# outin_shield_ethernet.net
KiCad netlist of a schematic drawn in EAGLE
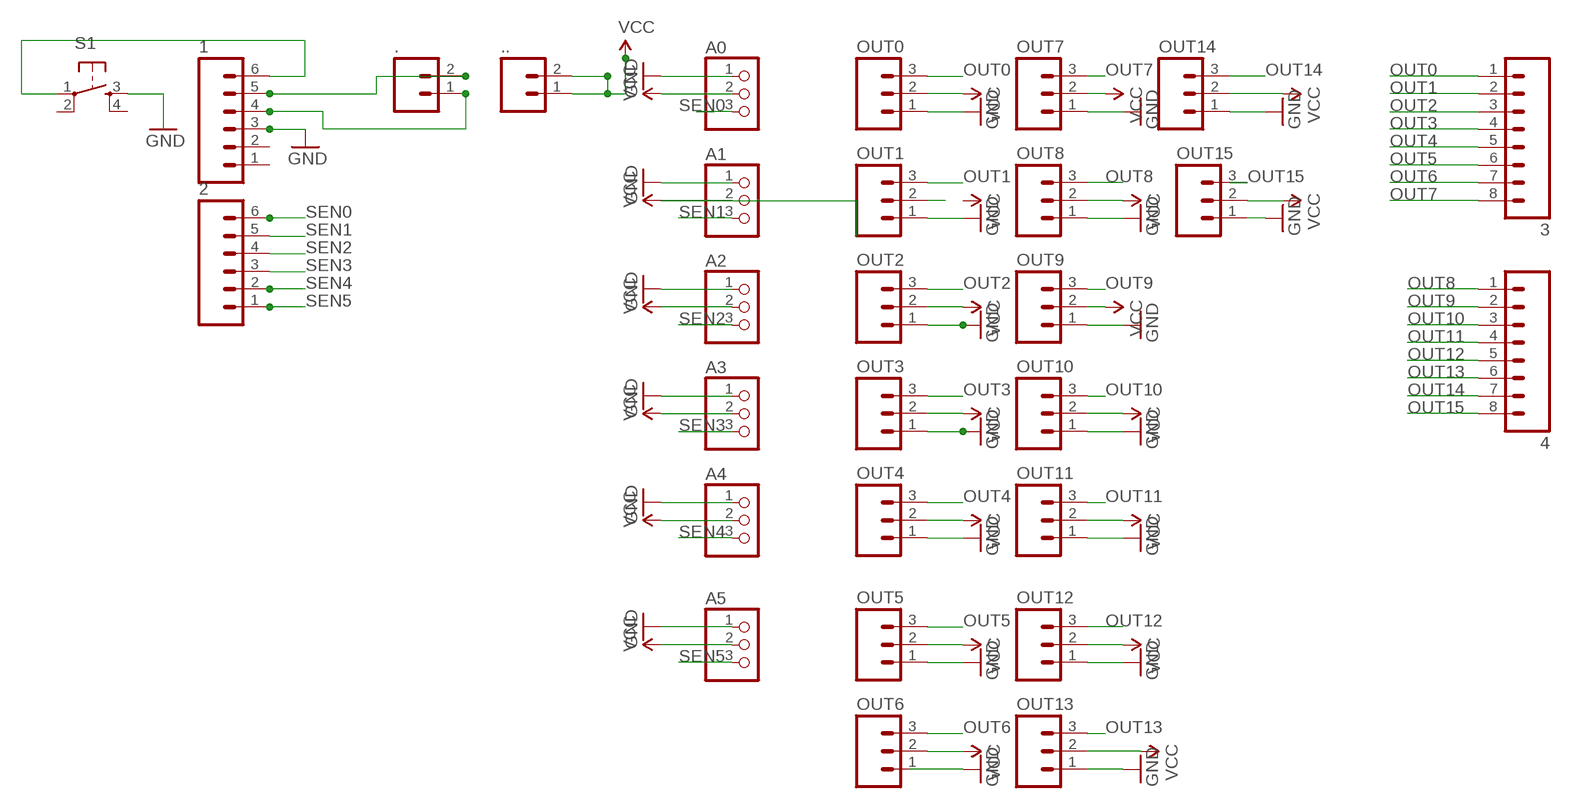
[diagram p0: schematic, sheet 1]

(export (version "E")
  (design (tool "Eeschema 10.0.6"))
  (components
    (comp (ref ".")
      (value "M02LOCK")
      (footprint "eagle-import:1X02_LOCK")
      (libsource (lib "eagle-import") (part "M02LOCK"))
    )
    (comp (ref "..")
      (value "M02LOCK")
      (footprint "eagle-import:1X02_LOCK")
      (libsource (lib "eagle-import") (part "M02LOCK"))
    )
    (comp (ref "1")
      (value "M06SIP")
      (footprint "eagle-import:1X06")
      (libsource (lib "eagle-import") (part "M06SIP"))
    )
    (comp (ref "2")
      (value "M06SIP")
      (footprint "eagle-import:1X06")
      (libsource (lib "eagle-import") (part "M06SIP"))
    )
    (comp (ref "3")
      (value "M081X08")
      (footprint "eagle-import:1X08")
      (libsource (lib "eagle-import") (part "M081X08"))
    )
    (comp (ref "4")
      (value "M081X08")
      (footprint "eagle-import:1X08")
      (libsource (lib "eagle-import") (part "M081X08"))
    )
    (comp (ref "A0")
      (value "PINHD-1X3")
      (footprint "eagle-import:1X03")
      (libsource (lib "eagle-import") (part "PINHD-1X3"))
    )
    (comp (ref "A1")
      (value "PINHD-1X3")
      (footprint "eagle-import:1X03")
      (libsource (lib "eagle-import") (part "PINHD-1X3"))
    )
    (comp (ref "A2")
      (value "PINHD-1X3")
      (footprint "eagle-import:1X03")
      (libsource (lib "eagle-import") (part "PINHD-1X3"))
    )
    (comp (ref "A3")
      (value "PINHD-1X3")
      (footprint "eagle-import:1X03")
      (libsource (lib "eagle-import") (part "PINHD-1X3"))
    )
    (comp (ref "A4")
      (value "PINHD-1X3")
      (footprint "eagle-import:1X03")
      (libsource (lib "eagle-import") (part "PINHD-1X3"))
    )
    (comp (ref "A5")
      (value "PINHD-1X3")
      (footprint "eagle-import:1X03")
      (libsource (lib "eagle-import") (part "PINHD-1X3"))
    )
    (comp (ref "OUT0")
      (value "M03PTH")
      (footprint "eagle-import:1X03")
      (libsource (lib "eagle-import") (part "M03PTH"))
    )
    (comp (ref "OUT1")
      (value "M03PTH")
      (footprint "eagle-import:1X03")
      (libsource (lib "eagle-import") (part "M03PTH"))
    )
    (comp (ref "OUT2")
      (value "M03PTH")
      (footprint "eagle-import:1X03")
      (libsource (lib "eagle-import") (part "M03PTH"))
    )
    (comp (ref "OUT3")
      (value "M03PTH")
      (footprint "eagle-import:1X03")
      (libsource (lib "eagle-import") (part "M03PTH"))
    )
    (comp (ref "OUT4")
      (value "M03PTH")
      (footprint "eagle-import:1X03")
      (libsource (lib "eagle-import") (part "M03PTH"))
    )
    (comp (ref "OUT5")
      (value "M03PTH")
      (footprint "eagle-import:1X03")
      (libsource (lib "eagle-import") (part "M03PTH"))
    )
    (comp (ref "OUT6")
      (value "M03PTH")
      (footprint "eagle-import:1X03")
      (libsource (lib "eagle-import") (part "M03PTH"))
    )
    (comp (ref "OUT7")
      (value "M03PTH")
      (footprint "eagle-import:1X03")
      (libsource (lib "eagle-import") (part "M03PTH"))
    )
    (comp (ref "OUT8")
      (value "M03PTH")
      (footprint "eagle-import:1X03")
      (libsource (lib "eagle-import") (part "M03PTH"))
    )
    (comp (ref "OUT9")
      (value "M03PTH")
      (footprint "eagle-import:1X03")
      (libsource (lib "eagle-import") (part "M03PTH"))
    )
    (comp (ref "OUT10")
      (value "M03PTH")
      (footprint "eagle-import:1X03")
      (libsource (lib "eagle-import") (part "M03PTH"))
    )
    (comp (ref "OUT11")
      (value "M03PTH")
      (footprint "eagle-import:1X03")
      (libsource (lib "eagle-import") (part "M03PTH"))
    )
    (comp (ref "OUT12")
      (value "M03PTH")
      (footprint "eagle-import:1X03")
      (libsource (lib "eagle-import") (part "M03PTH"))
    )
    (comp (ref "OUT13")
      (value "M03PTH")
      (footprint "eagle-import:1X03")
      (libsource (lib "eagle-import") (part "M03PTH"))
    )
    (comp (ref "OUT14")
      (value "M03PTH")
      (footprint "eagle-import:1X03")
      (libsource (lib "eagle-import") (part "M03PTH"))
    )
    (comp (ref "OUT15")
      (value "M03PTH")
      (footprint "eagle-import:1X03")
      (libsource (lib "eagle-import") (part "M03PTH"))
    )
    (comp (ref "S1")
      (value "TAC_SWITCHPTH")
      (footprint "eagle-import:TACTILE-PTH")
      (libsource (lib "eagle-import") (part "TAC_SWITCHPTH"))
    )
  )
  (nets
    (net (code "1") (name "/OUT0") (class "Default")
      (node (ref "3") (pin "1") (pinfunction "1_1") (pintype "passive"))
      (node (ref "OUT0") (pin "3") (pinfunction "3_3") (pintype "passive"))
    )
    (net (code "2") (name "/OUT1") (class "Default")
      (node (ref "3") (pin "2") (pinfunction "2_2") (pintype "passive"))
      (node (ref "OUT1") (pin "3") (pinfunction "3_3") (pintype "passive"))
    )
    (net (code "3") (name "/OUT2") (class "Default")
      (node (ref "3") (pin "3") (pinfunction "3_3") (pintype "passive"))
      (node (ref "OUT2") (pin "3") (pinfunction "3_3") (pintype "passive"))
    )
    (net (code "4") (name "/OUT3") (class "Default")
      (node (ref "3") (pin "4") (pinfunction "4_4") (pintype "passive"))
      (node (ref "OUT3") (pin "3") (pinfunction "3_3") (pintype "passive"))
    )
    (net (code "5") (name "/OUT4") (class "Default")
      (node (ref "3") (pin "5") (pinfunction "5_5") (pintype "passive"))
      (node (ref "OUT4") (pin "3") (pinfunction "3_3") (pintype "passive"))
    )
    (net (code "6") (name "/OUT5") (class "Default")
      (node (ref "3") (pin "6") (pinfunction "6_6") (pintype "passive"))
      (node (ref "OUT5") (pin "3") (pinfunction "3_3") (pintype "passive"))
    )
    (net (code "7") (name "/OUT6") (class "Default")
      (node (ref "3") (pin "7") (pinfunction "7_7") (pintype "passive"))
      (node (ref "OUT6") (pin "3") (pinfunction "3_3") (pintype "passive"))
    )
    (net (code "8") (name "/OUT7") (class "Default")
      (node (ref "3") (pin "8") (pinfunction "8_8") (pintype "passive"))
      (node (ref "OUT7") (pin "3") (pinfunction "3_3") (pintype "passive"))
    )
    (net (code "9") (name "/OUT8") (class "Default")
      (node (ref "4") (pin "1") (pinfunction "1_1") (pintype "passive"))
      (node (ref "OUT8") (pin "3") (pinfunction "3_3") (pintype "passive"))
    )
    (net (code "10") (name "/OUT9") (class "Default")
      (node (ref "4") (pin "2") (pinfunction "2_2") (pintype "passive"))
      (node (ref "OUT9") (pin "3") (pinfunction "3_3") (pintype "passive"))
    )
    (net (code "11") (name "/OUT10") (class "Default")
      (node (ref "4") (pin "3") (pinfunction "3_3") (pintype "passive"))
      (node (ref "OUT10") (pin "3") (pinfunction "3_3") (pintype "passive"))
    )
    (net (code "12") (name "/OUT11") (class "Default")
      (node (ref "4") (pin "4") (pinfunction "4_4") (pintype "passive"))
      (node (ref "OUT11") (pin "3") (pinfunction "3_3") (pintype "passive"))
    )
    (net (code "13") (name "/OUT12") (class "Default")
      (node (ref "4") (pin "5") (pinfunction "5_5") (pintype "passive"))
      (node (ref "OUT12") (pin "3") (pinfunction "3_3") (pintype "passive"))
    )
    (net (code "14") (name "/OUT13") (class "Default")
      (node (ref "4") (pin "6") (pinfunction "6_6") (pintype "passive"))
      (node (ref "OUT13") (pin "3") (pinfunction "3_3") (pintype "passive"))
    )
    (net (code "15") (name "/OUT14") (class "Default")
      (node (ref "4") (pin "7") (pinfunction "7_7") (pintype "passive"))
      (node (ref "OUT14") (pin "3") (pinfunction "3_3") (pintype "passive"))
    )
    (net (code "16") (name "/OUT15") (class "Default")
      (node (ref "4") (pin "8") (pinfunction "8_8") (pintype "passive"))
      (node (ref "OUT15") (pin "3") (pinfunction "3_3") (pintype "passive"))
    )
    (net (code "17") (name "/SEN0") (class "Default")
      (node (ref "2") (pin "6") (pinfunction "6_6") (pintype "passive"))
      (node (ref "A0") (pin "3") (pinfunction "3_3") (pintype "passive"))
    )
    (net (code "18") (name "/SEN1") (class "Default")
      (node (ref "2") (pin "5") (pinfunction "5_5") (pintype "passive"))
      (node (ref "A1") (pin "3") (pinfunction "3_3") (pintype "passive"))
    )
    (net (code "19") (name "/SEN2") (class "Default")
      (node (ref "2") (pin "4") (pinfunction "4_4") (pintype "passive"))
      (node (ref "A2") (pin "3") (pinfunction "3_3") (pintype "passive"))
    )
    (net (code "20") (name "/SEN3") (class "Default")
      (node (ref "2") (pin "3") (pinfunction "3_3") (pintype "passive"))
      (node (ref "A3") (pin "3") (pinfunction "3_3") (pintype "passive"))
    )
    (net (code "21") (name "/SEN4") (class "Default")
      (node (ref "2") (pin "2") (pinfunction "2_2") (pintype "passive"))
      (node (ref "A4") (pin "3") (pinfunction "3_3") (pintype "passive"))
    )
    (net (code "22") (name "/SEN5") (class "Default")
      (node (ref "2") (pin "1") (pinfunction "1_1") (pintype "passive"))
      (node (ref "A5") (pin "3") (pinfunction "3_3") (pintype "passive"))
    )
    (net (code "23") (name "GND") (class "Default")
      (node (ref "1") (pin "3") (pinfunction "3_3") (pintype "passive"))
      (node (ref "A0") (pin "1") (pinfunction "1_1") (pintype "passive"))
      (node (ref "A1") (pin "1") (pinfunction "1_1") (pintype "passive"))
      (node (ref "A2") (pin "1") (pinfunction "1_1") (pintype "passive"))
      (node (ref "A3") (pin "1") (pinfunction "1_1") (pintype "passive"))
      (node (ref "A4") (pin "1") (pinfunction "1_1") (pintype "passive"))
      (node (ref "A5") (pin "1") (pinfunction "1_1") (pintype "passive"))
      (node (ref "OUT0") (pin "1") (pinfunction "1_1") (pintype "passive"))
      (node (ref "OUT1") (pin "1") (pinfunction "1_1") (pintype "passive"))
      (node (ref "OUT10") (pin "1") (pinfunction "1_1") (pintype "passive"))
      (node (ref "OUT11") (pin "1") (pinfunction "1_1") (pintype "passive"))
      (node (ref "OUT12") (pin "1") (pinfunction "1_1") (pintype "passive"))
      (node (ref "OUT13") (pin "1") (pinfunction "1_1") (pintype "passive"))
      (node (ref "OUT14") (pin "1") (pinfunction "1_1") (pintype "passive"))
      (node (ref "OUT15") (pin "1") (pinfunction "1_1") (pintype "passive"))
      (node (ref "OUT2") (pin "1") (pinfunction "1_1") (pintype "passive"))
      (node (ref "OUT3") (pin "1") (pinfunction "1_1") (pintype "passive"))
      (node (ref "OUT4") (pin "1") (pinfunction "1_1") (pintype "passive"))
      (node (ref "OUT5") (pin "1") (pinfunction "1_1") (pintype "passive"))
      (node (ref "OUT7") (pin "1") (pinfunction "1_1") (pintype "passive"))
      (node (ref "OUT8") (pin "1") (pinfunction "1_1") (pintype "passive"))
      (node (ref "OUT9") (pin "1") (pinfunction "1_1") (pintype "passive"))
    )
    (net (code "24") (name "Net-(.-Pad1)") (class "Default")
      (node (ref ".") (pin "1") (pinfunction "1_1") (pintype "passive"))
      (node (ref "1") (pin "4") (pinfunction "4_4") (pintype "passive"))
    )
    (net (code "25") (name "Net-(.-Pad2)") (class "Default")
      (node (ref ".") (pin "2") (pinfunction "2_2") (pintype "passive"))
      (node (ref "1") (pin "5") (pinfunction "5_5") (pintype "passive"))
    )
    (net (code "26") (name "Net-(1-Pad6)") (class "Default")
      (node (ref "1") (pin "6") (pinfunction "6_6") (pintype "passive"))
      (node (ref "S1") (pin "1") (pinfunction "1_1") (pintype "passive"))
    )
    (net (code "27") (name "VCC") (class "Default")
      (node (ref "..") (pin "1") (pinfunction "1_1") (pintype "passive"))
      (node (ref "..") (pin "2") (pinfunction "2_2") (pintype "passive"))
      (node (ref "A0") (pin "2") (pinfunction "2_2") (pintype "passive"))
      (node (ref "A1") (pin "2") (pinfunction "2_2") (pintype "passive"))
      (node (ref "A2") (pin "2") (pinfunction "2_2") (pintype "passive"))
      (node (ref "A3") (pin "2") (pinfunction "2_2") (pintype "passive"))
      (node (ref "A4") (pin "2") (pinfunction "2_2") (pintype "passive"))
      (node (ref "A5") (pin "2") (pinfunction "2_2") (pintype "passive"))
      (node (ref "OUT0") (pin "2") (pinfunction "2_2") (pintype "passive"))
      (node (ref "OUT10") (pin "2") (pinfunction "2_2") (pintype "passive"))
      (node (ref "OUT11") (pin "2") (pinfunction "2_2") (pintype "passive"))
      (node (ref "OUT12") (pin "2") (pinfunction "2_2") (pintype "passive"))
      (node (ref "OUT13") (pin "2") (pinfunction "2_2") (pintype "passive"))
      (node (ref "OUT14") (pin "2") (pinfunction "2_2") (pintype "passive"))
      (node (ref "OUT15") (pin "2") (pinfunction "2_2") (pintype "passive"))
      (node (ref "OUT2") (pin "2") (pinfunction "2_2") (pintype "passive"))
      (node (ref "OUT3") (pin "2") (pinfunction "2_2") (pintype "passive"))
      (node (ref "OUT4") (pin "2") (pinfunction "2_2") (pintype "passive"))
      (node (ref "OUT5") (pin "2") (pinfunction "2_2") (pintype "passive"))
      (node (ref "OUT6") (pin "2") (pinfunction "2_2") (pintype "passive"))
      (node (ref "OUT7") (pin "2") (pinfunction "2_2") (pintype "passive"))
      (node (ref "OUT8") (pin "2") (pinfunction "2_2") (pintype "passive"))
      (node (ref "OUT9") (pin "2") (pinfunction "2_2") (pintype "passive"))
    )
    (net (code "28") (name "unconnected-(1-Pad1)") (class "Default")
      (node (ref "1") (pin "1") (pinfunction "1_1") (pintype "passive"))
    )
    (net (code "29") (name "unconnected-(1-Pad2)") (class "Default")
      (node (ref "1") (pin "2") (pinfunction "2_2") (pintype "passive"))
    )
    (net (code "30") (name "unconnected-(OUT1-Pad2)") (class "Default")
      (node (ref "OUT1") (pin "2") (pinfunction "2_2") (pintype "passive"))
    )
    (net (code "31") (name "unconnected-(OUT6-Pad1)") (class "Default")
      (node (ref "OUT6") (pin "1") (pinfunction "1_1") (pintype "passive"))
    )
    (net (code "32") (name "unconnected-(S1-Pad2)") (class "Default")
      (node (ref "S1") (pin "2") (pinfunction "2_2") (pintype "passive"))
    )
    (net (code "33") (name "unconnected-(S1-Pad3)") (class "Default")
      (node (ref "S1") (pin "3") (pinfunction "3_3") (pintype "passive"))
    )
    (net (code "34") (name "unconnected-(S1-Pad4)") (class "Default")
      (node (ref "S1") (pin "4") (pinfunction "4_4") (pintype "passive"))
    )
  )
)
